# Power-Sheet-2.net
KiCad netlist of a schematic drawn in Altium Designer
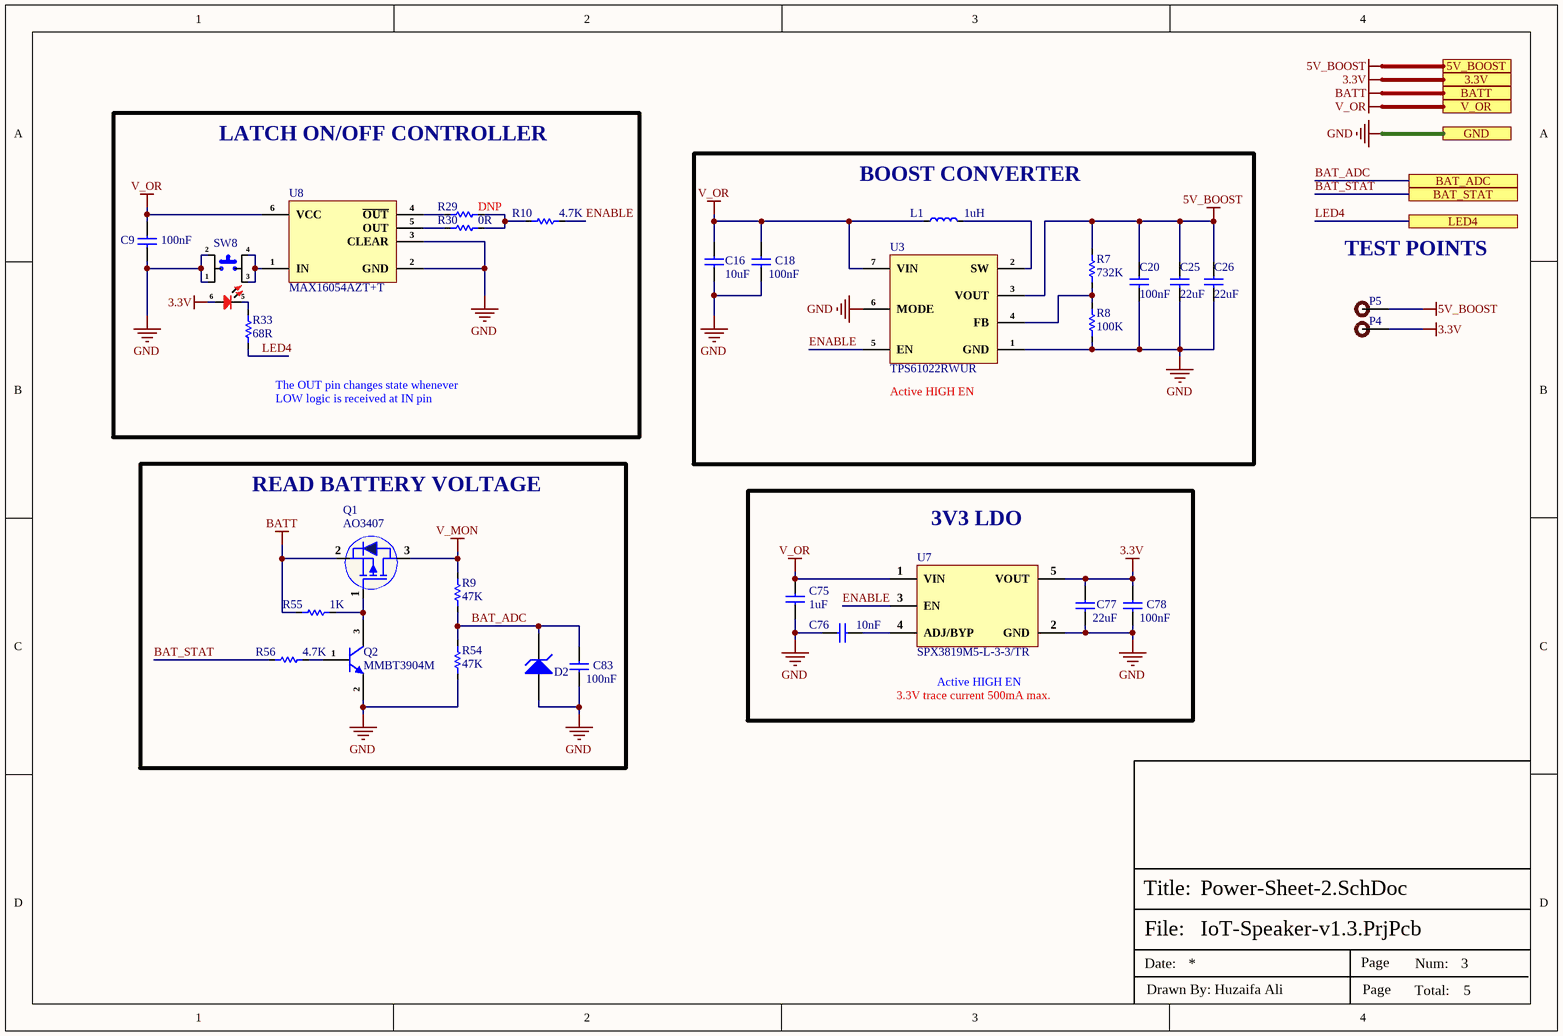
[diagram p0: Power-Sheet-2.SchDoc]

(export (version "E")
  (design (tool "Eeschema 10.0.6"))
  (components
    (comp (ref "C9")
      (value "100nF")
      (footprint "Cap-0402")
      (description "CAP CER 0.1UF 25V X5R 0402")
      (fields
        (field (name "MANUFACTURER") "Yageo")
        (field (name "MANUFACTURER PART NUMBER") "CC0402KRX5R8BB104")
      )
      (libsource (lib "eSpark_centralized_Library(2022)") (part "CC0402KRX5R8BB104"))
    )
    (comp (ref "C16")
      (value "10uF")
      (footprint "Cap-0805")
      (description "CAP CER 10UF 25V X5R 0805")
      (fields
        (field (name "MANUFACTURER") "Yageo")
        (field (name "MANUFACTURER PART NUMBER") "CC0805KKX5R8BB106")
      )
      (libsource (lib "eSpark_centralized_Library(2022)") (part "CC0805KKX5R8BB106"))
    )
    (comp (ref "C18")
      (value "100nF")
      (footprint "Cap-0402")
      (description "CAP CER 0.1UF 25V X5R 0402")
      (fields
        (field (name "MANUFACTURER") "Yageo")
        (field (name "MANUFACTURER PART NUMBER") "CC0402KRX5R8BB104")
      )
      (libsource (lib "eSpark_centralized_Library(2022)") (part "CC0402KRX5R8BB104"))
    )
    (comp (ref "C20")
      (value "100nF")
      (footprint "Cap-0402")
      (description "CAP CER 0.1UF 25V X5R 0402")
      (fields
        (field (name "MANUFACTURER") "Yageo")
        (field (name "MANUFACTURER PART NUMBER") "CC0402KRX5R8BB104")
      )
      (libsource (lib "eSpark_centralized_Library(2022)") (part "CC0402KRX5R8BB104"))
    )
    (comp (ref "C25")
      (value "22uF")
      (footprint "Cap-0603")
      (description "CAP CER 22UF 10V X5R 0603")
      (fields
        (field (name "MANUFACTURER") "Yageo")
        (field (name "MANUFACTURER PART NUMBER") "CC0603MRX5R6BB226")
      )
      (libsource (lib "eSpark_centralized_Library(2022)") (part "CC0603MRX5R6BB226"))
    )
    (comp (ref "C26")
      (value "22uF")
      (footprint "Cap-0603")
      (description "CAP CER 22UF 10V X5R 0603")
      (fields
        (field (name "MANUFACTURER") "Yageo")
        (field (name "MANUFACTURER PART NUMBER") "CC0603MRX5R6BB226")
      )
      (libsource (lib "eSpark_centralized_Library(2022)") (part "CC0603MRX5R6BB226"))
    )
    (comp (ref "C75")
      (value "1uF")
      (footprint "Cap-0603")
      (description "CAP CER 1UF 25V X5R 0603")
      (fields
        (field (name "MANUFACTURER") "Yageo")
        (field (name "MANUFACTURER PART NUMBER") "CC0603KRX5R8BB105")
      )
      (libsource (lib "eSpark_centralized_Library(2022)") (part "CC0603KRX5R8BB105"))
    )
    (comp (ref "C76")
      (value "10nF")
      (footprint "Cap-0603")
      (description "CAP CER 10000PF 50V C0G/NPO 0603")
      (fields
        (field (name "MANUFACTURER") "Yageo")
        (field (name "MANUFACTURER PART NUMBER") "CC0603JRNPO9BN103")
      )
      (libsource (lib "eSpark_centralized_Library(2022)") (part "CC0603JRNPO9BN103"))
    )
    (comp (ref "C77")
      (value "22uF")
      (footprint "Cap-0603")
      (description "CAP CER 22UF 10V X5R 0603")
      (fields
        (field (name "MANUFACTURER") "Yageo")
        (field (name "MANUFACTURER PART NUMBER") "CC0603MRX5R6BB226")
      )
      (libsource (lib "eSpark_centralized_Library(2022)") (part "CC0603MRX5R6BB226"))
    )
    (comp (ref "C78")
      (value "100nF")
      (footprint "Cap-0402")
      (description "CAP CER 0.1UF 25V X5R 0402")
      (fields
        (field (name "MANUFACTURER") "Yageo")
        (field (name "MANUFACTURER PART NUMBER") "CC0402KRX5R8BB104")
      )
      (libsource (lib "eSpark_centralized_Library(2022)") (part "CC0402KRX5R8BB104"))
    )
    (comp (ref "C83")
      (value "100nF")
      (footprint "Cap-0402")
      (description "CAP CER 0.1UF 25V X5R 0402")
      (fields
        (field (name "MANUFACTURER") "Yageo")
        (field (name "MANUFACTURER PART NUMBER") "CC0402KRX5R8BB104")
      )
      (libsource (lib "eSpark_centralized_Library(2022)") (part "CC0402KRX5R8BB104"))
    )
    (comp (ref "D2")
      (value "MM3Z3V3B")
      (footprint "SOD323F")
      (description "DIODE ZENER 3.3V 200MW SOD323F")
      (fields (field (name "MANUFACTURER") "ON Semiconductor / Fairchild") (field (name "TOLERANCE") "2%"))
      (libsource (lib "eSpark_centralized_Library(2022)") (part "MM3Z3V3B"))
    )
    (comp (ref "L1")
      (value "1uH")
      (footprint "MPIT6045-1R0N-LF")
      (description "5.15A 1uH ±30% SMD Power Inductors ROHS")
      (fields
        (field (name "MANUFACTURER") "microgate")
        (field (name "MANUFACTURER PART NUMBER") "MPIT6045-1R0N-LF")
      )
      (libsource (lib "eSpark_centralized_Library(2022)") (part "MPIT6045-1R0N-LF"))
    )
    (comp (ref "P4")
      (value "TEST POINT")
      (footprint "Test-point")
      (description "Test Point ON")
      (libsource (lib "eSpark_centralized_Library(2022)") (part "TEST POINT"))
    )
    (comp (ref "P5")
      (value "TEST POINT")
      (footprint "Test-point")
      (description "Test Point ON")
      (libsource (lib "eSpark_centralized_Library(2022)") (part "TEST POINT"))
    )
    (comp (ref "Q1")
      (value "AO3407")
      (footprint "SOT-23")
      (description "30V 4.1A 60mΩ@10V,4.1A 350mW 3V@250uA P Channel SOT-23 MOSFETs ROHS")
      (fields (field (name "MANUFACTURER") "Guangdong Hottech") (field (name "LCSC PART NUMBER") "C181093"))
      (libsource (lib "eSpark_centralized_Library(2022)") (part "AO3407"))
    )
    (comp (ref "Q2")
      (value "MMBT3904M")
      (footprint "SOT-723")
      (fields (field (name "MANUFACTURER") "TECH PUBLIC") (field (name "LCSC PART NUMBER") "C2923360"))
      (libsource (lib "eSpark_centralized_Library(2022)") (part "MMBT3904M"))
    )
    (comp (ref "R7")
      (value "732K")
      (footprint "Res-0402")
      (description "±1% 732kΩ 0402 Chip Resistor - Surface Mount ROHS")
      (fields
        (field (name "MANUFACTURER") "FOJAN")
        (field (name "MANUFACTURER PART NUMBER") "FRC0402F7323TS")
      )
      (libsource (lib "eSpark_centralized_Library(2022)") (part "FRC0402F7323TS"))
    )
    (comp (ref "R8")
      (value "100K")
      (footprint "Res-0603")
      (description "RES SMD 100K OHM 0.1% 1/10W 0603")
      (fields
        (field (name "MANUFACTURER") "Yageo")
        (field (name "MANUFACTURER PART NUMBER") "RT0603BRD07100KL")
      )
      (libsource (lib "eSpark_centralized_Library(2022)") (part "RT0603BRD07100KL"))
    )
    (comp (ref "R9")
      (value "47K")
      (footprint "Res-0603")
      (description "RES 47K OHM 5% 1/10W 0603")
      (fields
        (field (name "MANUFACTURER") "Yageo")
        (field (name "MANUFACTURER PART NUMBER") "RC0603JR-0747KL")
      )
      (libsource (lib "eSpark_centralized_Library(2022)") (part "RC0603JR-0747KL"))
    )
    (comp (ref "R10")
      (value "4.7K")
      (footprint "Res-0603")
      (description "RES SMD 4.7K OHM 5% 1/10W 0603")
      (fields
        (field (name "MANUFACTURER") "Yageo")
        (field (name "MANUFACTURER PART NUMBER") "RC0603JR-074K7L")
      )
      (libsource (lib "eSpark Libraries") (part "RC0603JR-074K7L"))
    )
    (comp (ref "R29")
      (value "DNP")
      (footprint "Res-0603")
      (description "RES SMD 0R, 1%, 0.1W, 0603")
      (fields
        (field (name "MANUFACTURER") "Yageo")
        (field (name "MANUFACTURER PART NUMBER") "RC0603FR-070RL")
      )
      (libsource (lib "eSpark Libraries") (part "RC0603FR-070RL"))
    )
    (comp (ref "R30")
      (value "0R")
      (footprint "Res-0603")
      (description "RES SMD 0R, 1%, 0.1W, 0603")
      (fields
        (field (name "MANUFACTURER") "Yageo")
        (field (name "MANUFACTURER PART NUMBER") "RC0603FR-070RL")
      )
      (libsource (lib "eSpark Libraries") (part "RC0603FR-070RL"))
    )
    (comp (ref "R33")
      (value "68R")
      (footprint "Res-0402")
      (description "RES SMD 68 OHM 0.1% 1/16W 0402")
      (fields
        (field (name "MANUFACTURER") "Panasonic")
        (field (name "MANUFACTURER PART NUMBER") "ERA-2AEB680X")
      )
      (libsource (lib "eSpark_centralized_Library(2022)") (part "ERA2AEB680X"))
    )
    (comp (ref "R54")
      (value "47K")
      (footprint "Res-0603")
      (description "RES 47K OHM 5% 1/10W 0603")
      (fields
        (field (name "MANUFACTURER") "Yageo")
        (field (name "MANUFACTURER PART NUMBER") "RC0603JR-0747KL")
      )
      (libsource (lib "eSpark_centralized_Library(2022)") (part "RC0603JR-0747KL"))
    )
    (comp (ref "R55")
      (value "1K")
      (footprint "Res-0603")
      (description "RES SMD 1K OHM 1% 1/10W 0603")
      (fields
        (field (name "MANUFACTURER") "Yageo")
        (field (name "MANUFACTURER PART NUMBER") "RC0603FR-071KL")
      )
      (libsource (lib "eSpark_centralized_Library(2022)") (part "RC0603FR-071KL"))
    )
    (comp (ref "R56")
      (value "4.7K")
      (footprint "Res-0603")
      (description "RES SMD 4.7K OHM 5% 1/10W 0603")
      (fields
        (field (name "MANUFACTURER") "Yageo")
        (field (name "MANUFACTURER PART NUMBER") "RC0603JR-074K7L")
      )
      (libsource (lib "eSpark_centralized_Library(2022)") (part "RC0603JR-074K7L"))
    )
    (comp (ref "SW8")
      (value "TL1260GQRBLK")
      (footprint "TL1260GQRBLK")
      (description "SWITCH TACTILE SPST-NO 0.05A 12V")
      (fields (field (name "MANUFACTURER") "E-Switch"))
      (libsource (lib "eSpark_centralized_Library(2022)") (part "TL1260GQRBLK"))
    )
    (comp (ref "U3")
      (value "TPS61022RWUR")
      (footprint "7-VQFN-HR (2x2)")
      (description "8-A boost converter with 0.5-V ultra-low input voltage 7-VQFN-HR -40 to 125")
      (fields (field (name "MANUFACTURER") "Texas Instruments") (field (name "LCSC PART NUMBER") "C915088"))
      (libsource (lib "Centralize") (part "TPS61022RWUR"))
    )
    (comp (ref "U7")
      (value "SPX3819M5-L-3-3/TR")
      (footprint "SOT-23-5")
      (description "SPX3819 Series 3.3 V 500 mA Fixed Output SMT LDO Regulator - SOT-23-5")
      (fields (field (name "MANUFACTURER") "MaxLinear") (field (name "LCSC PART NUMBER") "C9055"))
      (libsource (lib "eSpark_centralized_Library(2022)") (part "SPX3819M5-L-3-3/TR"))
    )
    (comp (ref "U8")
      (value "MAX16054AZT+T")
      (footprint "TSOT-23-6")
      (description "IC CNTRLR ON/OFF W/DEB TSOT23-6")
      (fields (field (name "MANUFACTURER") "Maxim") (field (name "LCSC PART NUMBER") "C79401"))
      (libsource (lib "eSpark_centralized_Library(2022)") (part "MAX16054AZT+T"))
    )
  )
  (nets
    (net (code "1") (name "/BAT_ADC") (class "Default")
      (node (ref "C83") (pin "2") (pinfunction "2_2") (pintype "passive"))
      (node (ref "D2") (pin "2") (pinfunction "K_2") (pintype "passive"))
      (node (ref "R54") (pin "2") (pinfunction "2_2") (pintype "passive"))
      (node (ref "R9") (pin "1") (pinfunction "1_1") (pintype "passive"))
    )
    (net (code "2") (name "/BAT_STAT") (class "Default")
      (node (ref "R56") (pin "1") (pinfunction "1_1") (pintype "passive"))
    )
    (net (code "3") (name "/ENABLE") (class "Default")
      (node (ref "R10") (pin "2") (pinfunction "2_2") (pintype "passive"))
      (node (ref "U3") (pin "5") (pinfunction "EN_5") (pintype "passive"))
      (node (ref "U7") (pin "3") (pinfunction "EN_3") (pintype "passive"))
    )
    (net (code "4") (name "/LED4") (class "Default")
      (node (ref "R33") (pin "2") (pinfunction "2_2") (pintype "passive"))
    )
    (net (code "5") (name "3.3V") (class "Default")
      (node (ref "C77") (pin "2") (pinfunction "2_2") (pintype "passive"))
      (node (ref "C78") (pin "2") (pinfunction "2_2") (pintype "passive"))
      (node (ref "P4") (pin "1") (pinfunction "1_1") (pintype "passive"))
      (node (ref "SW8") (pin "6") (pinfunction "+_6") (pintype "passive"))
      (node (ref "U7") (pin "5") (pinfunction "VOUT_5") (pintype "passive"))
    )
    (net (code "6") (name "5V_BOOST") (class "Default")
      (node (ref "C20") (pin "2") (pinfunction "2_2") (pintype "passive"))
      (node (ref "C25") (pin "2") (pinfunction "2_2") (pintype "passive"))
      (node (ref "C26") (pin "2") (pinfunction "2_2") (pintype "passive"))
      (node (ref "P5") (pin "1") (pinfunction "1_1") (pintype "passive"))
      (node (ref "R7") (pin "2") (pinfunction "2_2") (pintype "passive"))
      (node (ref "U3") (pin "3") (pinfunction "VOUT_3") (pintype "passive"))
    )
    (net (code "7") (name "BATT") (class "Default")
      (node (ref "Q1") (pin "2") (pinfunction "S_2") (pintype "passive"))
      (node (ref "R55") (pin "1") (pinfunction "1_1") (pintype "passive"))
    )
    (net (code "8") (name "GND") (class "Default")
      (node (ref "C16") (pin "1") (pinfunction "1_1") (pintype "passive"))
      (node (ref "C18") (pin "1") (pinfunction "1_1") (pintype "passive"))
      (node (ref "C20") (pin "1") (pinfunction "1_1") (pintype "passive"))
      (node (ref "C25") (pin "1") (pinfunction "1_1") (pintype "passive"))
      (node (ref "C26") (pin "1") (pinfunction "1_1") (pintype "passive"))
      (node (ref "C75") (pin "1") (pinfunction "1_1") (pintype "passive"))
      (node (ref "C76") (pin "1") (pinfunction "1_1") (pintype "passive"))
      (node (ref "C77") (pin "1") (pinfunction "1_1") (pintype "passive"))
      (node (ref "C78") (pin "1") (pinfunction "1_1") (pintype "passive"))
      (node (ref "C83") (pin "1") (pinfunction "1_1") (pintype "passive"))
      (node (ref "C9") (pin "1") (pinfunction "1_1") (pintype "passive"))
      (node (ref "D2") (pin "1") (pinfunction "A_1") (pintype "passive"))
      (node (ref "Q2") (pin "2") (pinfunction "E_2") (pintype "passive"))
      (node (ref "R54") (pin "1") (pinfunction "1_1") (pintype "passive"))
      (node (ref "R8") (pin "1") (pinfunction "1_1") (pintype "passive"))
      (node (ref "SW8") (pin "1") (pinfunction "1_1") (pintype "passive"))
      (node (ref "SW8") (pin "2") (pinfunction "2_2") (pintype "passive"))
      (node (ref "U3") (pin "1") (pinfunction "GND_1") (pintype "passive"))
      (node (ref "U3") (pin "6") (pinfunction "MODE_6") (pintype "passive"))
      (node (ref "U7") (pin "2") (pinfunction "GND_2") (pintype "passive"))
      (node (ref "U8") (pin "2") (pinfunction "GND_2") (pintype "passive"))
      (node (ref "U8") (pin "3") (pinfunction "CLEAR_3") (pintype "passive"))
    )
    (net (code "9") (name "Net-(Q1-G)") (class "Default")
      (node (ref "Q1") (pin "1") (pinfunction "G_1") (pintype "passive"))
      (node (ref "Q2") (pin "3") (pinfunction "C_3") (pintype "passive"))
      (node (ref "R55") (pin "2") (pinfunction "2_2") (pintype "passive"))
    )
    (net (code "10") (name "Net-(Q2-B)") (class "Default")
      (node (ref "Q2") (pin "1") (pinfunction "B_1") (pintype "passive"))
      (node (ref "R56") (pin "2") (pinfunction "2_2") (pintype "passive"))
    )
    (net (code "11") (name "Net-(R10-Pad1)") (class "Default")
      (node (ref "R10") (pin "1") (pinfunction "1_1") (pintype "passive"))
      (node (ref "R29") (pin "2") (pinfunction "2_2") (pintype "passive"))
      (node (ref "R30") (pin "2") (pinfunction "2_2") (pintype "passive"))
    )
    (net (code "12") (name "Net-(SW8--)") (class "Default")
      (node (ref "R33") (pin "1") (pinfunction "1_1") (pintype "passive"))
      (node (ref "SW8") (pin "5") (pinfunction "-_5") (pintype "passive"))
    )
    (net (code "13") (name "Net-(U3-FB)") (class "Default")
      (node (ref "R7") (pin "1") (pinfunction "1_1") (pintype "passive"))
      (node (ref "R8") (pin "2") (pinfunction "2_2") (pintype "passive"))
      (node (ref "U3") (pin "4") (pinfunction "FB_4") (pintype "passive"))
    )
    (net (code "14") (name "Net-(U3-SW)") (class "Default")
      (node (ref "L1") (pin "2") (pinfunction "2_2") (pintype "passive"))
      (node (ref "U3") (pin "2") (pinfunction "SW_2") (pintype "passive"))
    )
    (net (code "15") (name "Net-(U7-ADJ{slash}BYP)") (class "Default")
      (node (ref "C76") (pin "2") (pinfunction "2_2") (pintype "passive"))
      (node (ref "U7") (pin "4") (pinfunction "ADJ/BYP_4") (pintype "passive"))
    )
    (net (code "16") (name "Net-(U8-IN)") (class "Default")
      (node (ref "SW8") (pin "3") (pinfunction "3_3") (pintype "passive"))
      (node (ref "SW8") (pin "4") (pinfunction "4_4") (pintype "passive"))
      (node (ref "U8") (pin "1") (pinfunction "IN_1") (pintype "passive"))
    )
    (net (code "17") (name "Net-(U8-OUT)") (class "Default")
      (node (ref "R30") (pin "1") (pinfunction "1_1") (pintype "passive"))
      (node (ref "U8") (pin "5") (pinfunction "OUT_5") (pintype "passive"))
    )
    (net (code "18") (name "Net-(U8-~{OUT})") (class "Default")
      (node (ref "R29") (pin "1") (pinfunction "1_1") (pintype "passive"))
      (node (ref "U8") (pin "4") (pinfunction "~{OUT}_4") (pintype "passive"))
    )
    (net (code "19") (name "V_MON") (class "Default")
      (node (ref "Q1") (pin "3") (pinfunction "D_3") (pintype "passive"))
      (node (ref "R9") (pin "2") (pinfunction "2_2") (pintype "passive"))
    )
    (net (code "20") (name "V_OR") (class "Default")
      (node (ref "C16") (pin "2") (pinfunction "2_2") (pintype "passive"))
      (node (ref "C18") (pin "2") (pinfunction "2_2") (pintype "passive"))
      (node (ref "C75") (pin "2") (pinfunction "2_2") (pintype "passive"))
      (node (ref "C9") (pin "2") (pinfunction "2_2") (pintype "passive"))
      (node (ref "L1") (pin "1") (pinfunction "1_1") (pintype "passive"))
      (node (ref "U3") (pin "7") (pinfunction "VIN_7") (pintype "passive"))
      (node (ref "U7") (pin "1") (pinfunction "VIN_1") (pintype "passive"))
      (node (ref "U8") (pin "6") (pinfunction "VCC_6") (pintype "passive"))
    )
  )
)
